# psu_switch.net
KiCad netlist of a schematic drawn in EAGLE
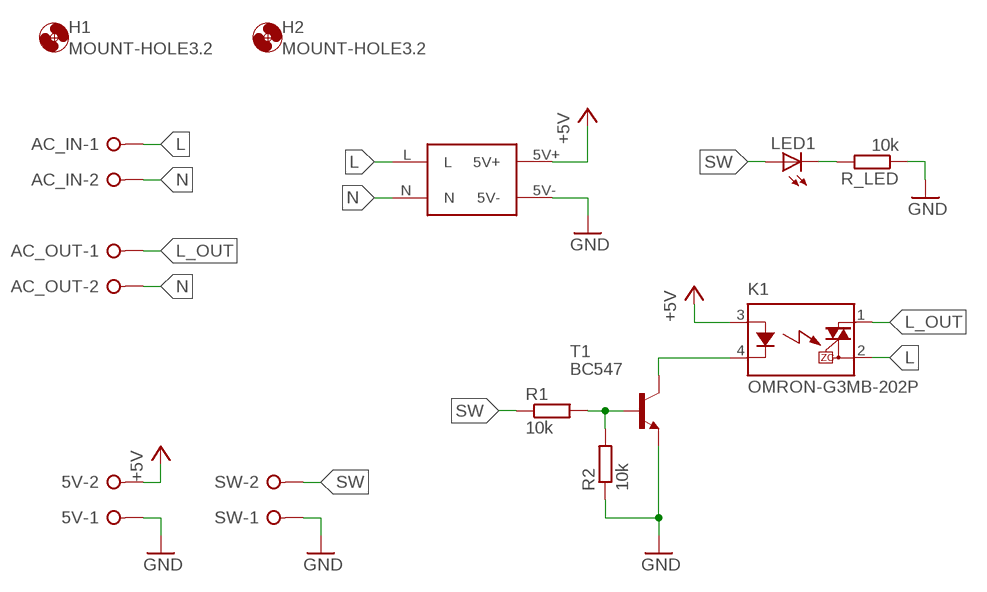
[diagram p0: schematic, sheet 1]

(export (version "E")
  (design (tool "Eeschema 10.0.6"))
  (components
    (comp (ref "5V")
      (value "W237-02P")
      (footprint "eagle-import:W237-132")
      (libsource (lib "eagle-import") (part "W237-02P"))
    )
    (comp (ref "AC_IN")
      (value "W237-02P")
      (footprint "eagle-import:W237-132")
      (libsource (lib "eagle-import") (part "W237-02P"))
    )
    (comp (ref "AC_OUT")
      (value "W237-02P")
      (footprint "eagle-import:W237-132")
      (libsource (lib "eagle-import") (part "W237-02P"))
    )
    (comp (ref "H1")
      (value "MOUNT-HOLE3.2")
      (footprint "eagle-import:3,2")
      (libsource (lib "eagle-import") (part "MOUNT-HOLE3.2"))
    )
    (comp (ref "H2")
      (value "MOUNT-HOLE3.2")
      (footprint "eagle-import:3,2")
      (libsource (lib "eagle-import") (part "MOUNT-HOLE3.2"))
    )
    (comp (ref "K1")
      (value "OMRON-G3MB-202P")
      (footprint "eagle-import:OMRON-G3MB-202P-SSR")
      (libsource (lib "eagle-import") (part "OMRON-G3MB-202P-SSR"))
    )
    (comp (ref "LED1")
      (value "LED3MM")
      (footprint "eagle-import:LED3MM")
      (libsource (lib "eagle-import") (part "LED3MM"))
    )
    (comp (ref "R1")
      (value "10k")
      (footprint "eagle-import:0207_10")
      (libsource (lib "eagle-import") (part "R-EU_0207/10"))
    )
    (comp (ref "R2")
      (value "10k")
      (footprint "eagle-import:0207_10")
      (libsource (lib "eagle-import") (part "R-EU_0207/10"))
    )
    (comp (ref "R_LED")
      (value "10k")
      (footprint "eagle-import:0207_10")
      (libsource (lib "eagle-import") (part "R-EU_0207/10"))
    )
    (comp (ref "SW")
      (value "W237-02P")
      (footprint "eagle-import:W237-132")
      (libsource (lib "eagle-import") (part "W237-02P"))
    )
    (comp (ref "T1")
      (value "BC547")
      (footprint "eagle-import:TO92")
      (libsource (lib "eagle-import") (part "BC547"))
    )
    (comp (ref "U$1")
      (value "700MA-STEP-DOWN")
      (footprint "eagle-import:700MA-STEP-DOWN")
      (libsource (lib "eagle-import") (part "700MA-STEP-DOWN"))
    )
  )
  (nets
    (net (code "1") (name "+5V") (class "Default")
      (node (ref "5V") (pin "2") (pinfunction "KL_2") (pintype "passive"))
      (node (ref "K1") (pin "3") (pinfunction "A_3") (pintype "passive"))
      (node (ref "U$1") (pin "5V+") (pinfunction "5V+_5V+") (pintype "bidirectional"))
    )
    (net (code "2") (name "GND") (class "Default")
      (node (ref "5V") (pin "1") (pinfunction "KL_1") (pintype "passive"))
      (node (ref "R2") (pin "1") (pinfunction "1_1") (pintype "passive"))
      (node (ref "R_LED") (pin "1") (pinfunction "1_1") (pintype "passive"))
      (node (ref "SW") (pin "1") (pinfunction "KL_1") (pintype "passive"))
      (node (ref "T1") (pin "1") (pinfunction "E_1") (pintype "passive"))
      (node (ref "U$1") (pin "5V-") (pinfunction "5V-_5V-") (pintype "bidirectional"))
    )
    (net (code "3") (name "L") (class "Default")
      (node (ref "AC_IN") (pin "1") (pinfunction "KL_1") (pintype "passive"))
      (node (ref "K1") (pin "2") (pinfunction "DS2_2") (pintype "passive"))
      (node (ref "U$1") (pin "L") (pinfunction "L_L") (pintype "bidirectional"))
    )
    (net (code "4") (name "L_OUT") (class "Default")
      (node (ref "AC_OUT") (pin "1") (pinfunction "KL_1") (pintype "passive"))
      (node (ref "K1") (pin "1") (pinfunction "DS1_1") (pintype "passive"))
    )
    (net (code "5") (name "N") (class "Default")
      (node (ref "AC_IN") (pin "2") (pinfunction "KL_2") (pintype "passive"))
      (node (ref "AC_OUT") (pin "2") (pinfunction "KL_2") (pintype "passive"))
      (node (ref "U$1") (pin "N") (pinfunction "N_N") (pintype "bidirectional"))
    )
    (net (code "6") (name "Net-(K1-K)") (class "Default")
      (node (ref "K1") (pin "4") (pinfunction "K_4") (pintype "passive"))
      (node (ref "T1") (pin "3") (pinfunction "C_3") (pintype "passive"))
    )
    (net (code "7") (name "Net-(LED1-C)") (class "Default")
      (node (ref "LED1") (pin "K") (pinfunction "C_K") (pintype "passive"))
      (node (ref "R_LED") (pin "2") (pinfunction "2_2") (pintype "passive"))
    )
    (net (code "8") (name "Net-(T1-B)") (class "Default")
      (node (ref "R1") (pin "2") (pinfunction "2_2") (pintype "passive"))
      (node (ref "R2") (pin "2") (pinfunction "2_2") (pintype "passive"))
      (node (ref "T1") (pin "2") (pinfunction "B_2") (pintype "passive"))
    )
    (net (code "9") (name "SW") (class "Default")
      (node (ref "LED1") (pin "A") (pinfunction "A_A") (pintype "passive"))
      (node (ref "R1") (pin "1") (pinfunction "1_1") (pintype "passive"))
      (node (ref "SW") (pin "2") (pinfunction "KL_2") (pintype "passive"))
    )
  )
)
